# TopSheet.net
KiCad netlist of a schematic drawn in Altium Designer
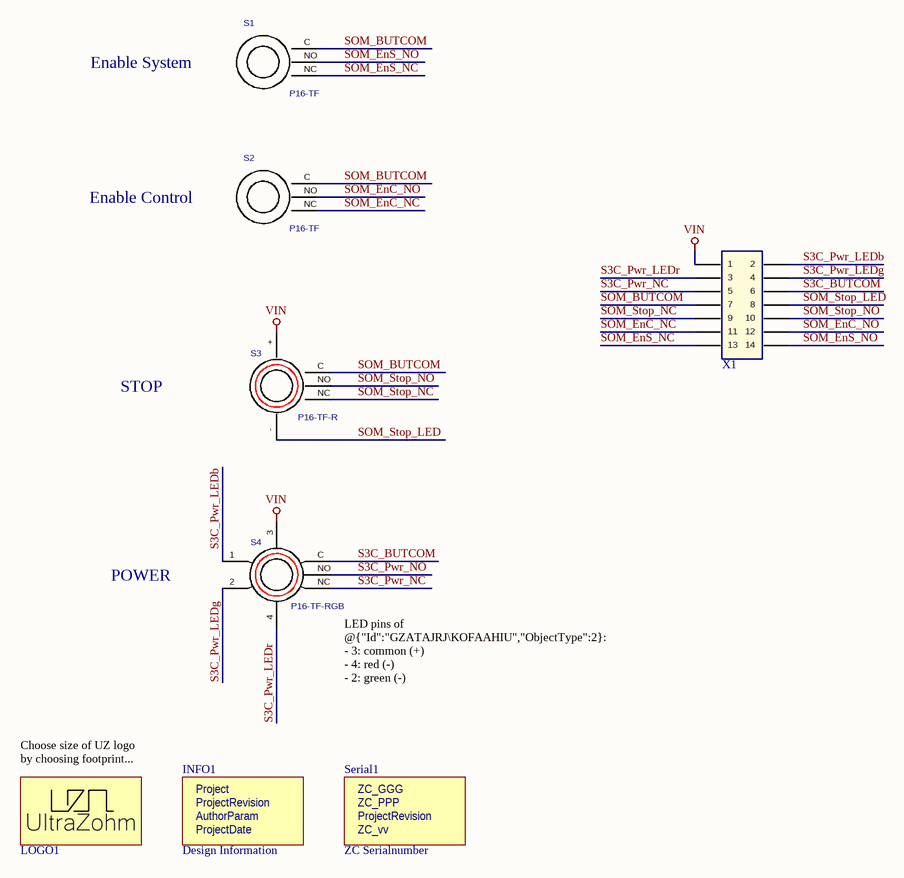
[diagram p0: TopSheet.SchDoc]

(export (version "E")
  (design (tool "Eeschema 10.0.6"))
  (components
    (comp (ref "INFO1")
      (value "Design Information")
      (footprint "Design_info2")
      (fields (field (name "MANUFACTURER") "UltraZohm") (field (name "CREATED FROM") "MGremer"))
      (libsource (lib "user") (part "Design_info"))
    )
    (comp (ref "LOGO1")
      (value "UZ Logo")
      (footprint "UZ_Logo_tiny")
      (description "Official Project Logo of the UltraZohm")
      (fields
        (field (name "MANUFACTURER") "PCB Manufacturer")
        (field (name "MANUFACTURER PART NUMBER") "UltraZohm Logo")
        (field (name "CREATED FROM") "T. Wendt")
      )
      (libsource (lib "user") (part "UZ_LOGO"))
    )
    (comp (ref "S1")
      (value "P16-TF")
      (footprint "P16-TF")
      (description "Stainless steel push botton 0.63 inch flat")
      (fields (field (name "MANUFACTURER") "Metzler") (field (name "CREATED FROM") "MGremer"))
      (libsource (lib "user") (part "P16-TR"))
    )
    (comp (ref "S2")
      (value "P16-TF")
      (footprint "P16-TF")
      (description "Stainless steel push botton 0.63 inch flat")
      (fields (field (name "MANUFACTURER") "Metzler") (field (name "CREATED FROM") "MGremer"))
      (libsource (lib "user") (part "P16-TR"))
    )
    (comp (ref "S3")
      (value "P16-TF-R")
      (footprint "P16-TF-R")
      (description "Stainless steel push botton 0.63 inch flat LED Ring red")
      (fields (field (name "MANUFACTURER") "Metzler") (field (name "CREATED FROM") "MGremer"))
      (libsource (lib "user") (part "P16-TR-R"))
    )
    (comp (ref "S4")
      (value "P16-TF-RGB")
      (footprint "P16-TF-RGB")
      (fields (field (name "MANUFACTURER") "Metzler") (field (name "CREATED FROM") "FRosner"))
      (libsource (lib "user") (part "P16-TF-RGB"))
    )
    (comp (ref "Serial1")
      (value "ZC Serialnumber")
      (footprint "ZC-Serial")
      (fields
        (field (name "MANUFACTURER PART NUMBER") "ZC-Serial")
        (field (name "MANUFACTURER") "UltraZohm")
        (field (name "CREATED FROM") "FRosner")
      )
      (libsource (lib "user") (part "ZC_Serial"))
    )
    (comp (ref "X1")
      (value "~")
      (footprint "TSW-107-07-XXX-S")
      (description "[low-cost] TSW-107-07-S-D Headers & Wire Housings Classic PCB Header Strips, 0.100\" pitch")
      (fields
        (field (name "MANUFACTURER PART NUMBER") "2.54-2*7P Pin Header")
        (field (name "MANUFACTURER") "Boom Precision Elec")
        (field (name "CREATED FROM") "FRosner")
      )
      (libsource (lib "user") (part "TSW-107-07-S-D"))
    )
  )
  (nets
    (net (code "1") (name "/S3C_BUTCOM") (class "Default")
      (node (ref "S4") (pin "C") (pinfunction "C_C") (pintype "passive"))
      (node (ref "X1") (pin "6") (pinfunction "6_6") (pintype "passive"))
    )
    (net (code "2") (name "/S3C_Pwr_LEDb") (class "Default")
      (node (ref "S4") (pin "1") (pinfunction "1_1") (pintype "passive"))
      (node (ref "X1") (pin "2") (pinfunction "2_2") (pintype "passive"))
    )
    (net (code "3") (name "/S3C_Pwr_LEDg") (class "Default")
      (node (ref "S4") (pin "2") (pinfunction "2_2") (pintype "passive"))
      (node (ref "X1") (pin "4") (pinfunction "4_4") (pintype "passive"))
    )
    (net (code "4") (name "/S3C_Pwr_LEDr") (class "Default")
      (node (ref "S4") (pin "4") (pinfunction "4_4") (pintype "passive"))
      (node (ref "X1") (pin "3") (pinfunction "3_3") (pintype "passive"))
    )
    (net (code "5") (name "/S3C_Pwr_NC") (class "Default")
      (node (ref "S4") (pin "NC") (pinfunction "NC_NC") (pintype "passive"))
      (node (ref "X1") (pin "5") (pinfunction "5_5") (pintype "passive"))
    )
    (net (code "6") (name "/S3C_Pwr_NO") (class "Default")
      (node (ref "S4") (pin "NO") (pinfunction "NO_NO") (pintype "passive"))
    )
    (net (code "7") (name "/SOM_BUTCOM") (class "Default")
      (node (ref "S1") (pin "C") (pinfunction "C_C") (pintype "passive"))
      (node (ref "S2") (pin "C") (pinfunction "C_C") (pintype "passive"))
      (node (ref "S3") (pin "C") (pinfunction "C_C") (pintype "passive"))
      (node (ref "X1") (pin "7") (pinfunction "7_7") (pintype "passive"))
    )
    (net (code "8") (name "/SOM_EnC_NC") (class "Default")
      (node (ref "S2") (pin "NC") (pinfunction "NC_NC") (pintype "passive"))
      (node (ref "X1") (pin "11") (pinfunction "11_11") (pintype "passive"))
    )
    (net (code "9") (name "/SOM_EnC_NO") (class "Default")
      (node (ref "S2") (pin "NO") (pinfunction "NO_NO") (pintype "passive"))
      (node (ref "X1") (pin "12") (pinfunction "12_12") (pintype "passive"))
    )
    (net (code "10") (name "/SOM_EnS_NC") (class "Default")
      (node (ref "S1") (pin "NC") (pinfunction "NC_NC") (pintype "passive"))
      (node (ref "X1") (pin "13") (pinfunction "13_13") (pintype "passive"))
    )
    (net (code "11") (name "/SOM_EnS_NO") (class "Default")
      (node (ref "S1") (pin "NO") (pinfunction "NO_NO") (pintype "passive"))
      (node (ref "X1") (pin "14") (pinfunction "14_14") (pintype "passive"))
    )
    (net (code "12") (name "/SOM_Stop_LED") (class "Default")
      (node (ref "S3") (pin "-") (pinfunction "-_-") (pintype "passive"))
      (node (ref "X1") (pin "8") (pinfunction "8_8") (pintype "passive"))
    )
    (net (code "13") (name "/SOM_Stop_NC") (class "Default")
      (node (ref "S3") (pin "NC") (pinfunction "NC_NC") (pintype "passive"))
      (node (ref "X1") (pin "9") (pinfunction "9_9") (pintype "passive"))
    )
    (net (code "14") (name "/SOM_Stop_NO") (class "Default")
      (node (ref "S3") (pin "NO") (pinfunction "NO_NO") (pintype "passive"))
      (node (ref "X1") (pin "10") (pinfunction "10_10") (pintype "passive"))
    )
    (net (code "15") (name "VIN") (class "Default")
      (node (ref "S3") (pin "+") (pinfunction "+_+") (pintype "passive"))
      (node (ref "S4") (pin "3") (pinfunction "3_3") (pintype "passive"))
      (node (ref "X1") (pin "1") (pinfunction "1_1") (pintype "passive"))
    )
  )
)
